# Display.net
KiCad netlist of a schematic drawn in Altium Designer
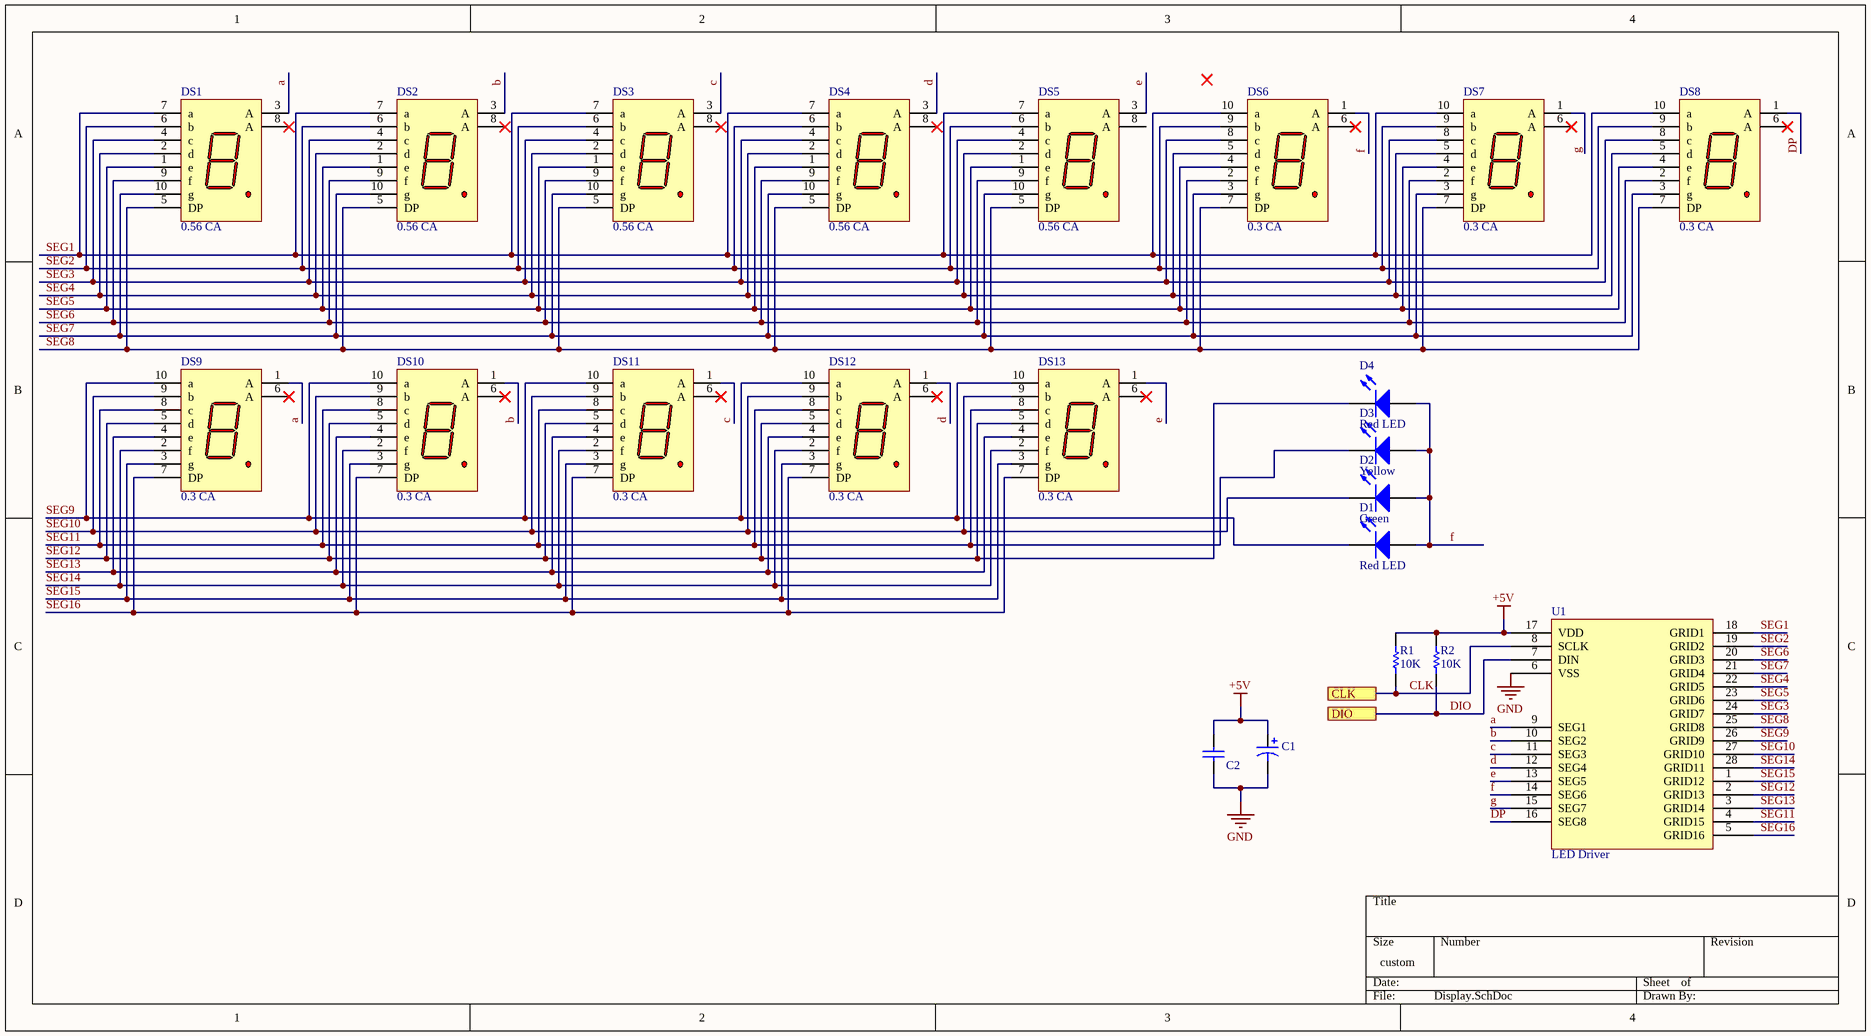
[diagram p0: Display.SchDoc]

(export (version "E")
  (design (tool "Eeschema 10.0.6"))
  (components
    (comp (ref "C1")
      (value "100uF/16V")
      (footprint "C10uF25V")
      (description "100uF/16V Electrolytic Capacitor")
      (fields (field (name "MANUFACTURER PART NUMBER") "Standard"))
      (libsource (lib "Ravi") (part "Capacitor_Electrolytic"))
    )
    (comp (ref "C2")
      (value "0.1uF/50V")
      (footprint "C0603")
      (description "CAP CER 0.1UF 50V X7R 0603")
      (fields (field (name "MANUFACTURER PART NUMBER") "0603B104K500CT"))
      (libsource (lib "Devices") (part "Capacitor_Ceramic"))
    )
    (comp (ref "D1")
      (value "Red LED")
      (footprint "LED-5mm")
      (description "Red 645nm LED Indication - Discrete 2.1V Radial")
      (fields (field (name "MANUFACTURER PART NUMBER") "Standard"))
      (libsource (lib "Ravi") (part "LED"))
    )
    (comp (ref "D2")
      (value "Green")
      (footprint "LED-5mm")
      (description "Green 568nm LED Indication - Discrete 2.2V Radial")
      (fields (field (name "MANUFACTURER PART NUMBER") "Standard"))
      (libsource (lib "Ravi") (part "LED"))
    )
    (comp (ref "D3")
      (value "Yellow")
      (footprint "LED-5mm")
      (description "Yellow 585nm LED Indication - Discrete 1.8V Radial")
      (fields (field (name "MANUFACTURER PART NUMBER") "Standard"))
      (libsource (lib "Ravi") (part "LED"))
    )
    (comp (ref "D4")
      (value "Red LED")
      (footprint "LED-5mm")
      (description "Red 645nm LED Indication - Discrete 2.1V Radial")
      (fields (field (name "MANUFACTURER PART NUMBER") "Standard"))
      (libsource (lib "Ravi") (part "LED"))
    )
    (comp (ref "DS1")
      (value "0.56 CA")
      (footprint "7Segment(0.56)")
      (description "DISPLAY 7SEG 0.56\" RED 10DIP")
      (fields (field (name "MANUFACTURER PART NUMBER") "Standard"))
      (libsource (lib "Ravi") (part "7 Segment_CA_0.56"))
    )
    (comp (ref "DS2")
      (value "0.56 CA")
      (footprint "7Segment(0.56)")
      (description "DISPLAY 7SEG 0.56\" RED 10DIP")
      (fields (field (name "MANUFACTURER PART NUMBER") "Standard"))
      (libsource (lib "Ravi") (part "7 Segment_CA_0.56"))
    )
    (comp (ref "DS3")
      (value "0.56 CA")
      (footprint "7Segment(0.56)")
      (description "DISPLAY 7SEG 0.56\" RED 10DIP")
      (fields (field (name "MANUFACTURER PART NUMBER") "Standard"))
      (libsource (lib "Ravi") (part "7 Segment_CA_0.56"))
    )
    (comp (ref "DS4")
      (value "0.56 CA")
      (footprint "7Segment(0.56)")
      (description "DISPLAY 7SEG 0.56\" RED 10DIP")
      (fields (field (name "MANUFACTURER PART NUMBER") "Standard"))
      (libsource (lib "Ravi") (part "7 Segment_CA_0.56"))
    )
    (comp (ref "DS5")
      (value "0.56 CA")
      (footprint "7Segment(0.56)")
      (description "DISPLAY 7SEG 0.56\" RED 10DIP")
      (fields (field (name "MANUFACTURER PART NUMBER") "Standard"))
      (libsource (lib "Ravi") (part "7 Segment_CA_0.56"))
    )
    (comp (ref "DS6")
      (value "0.3 CA")
      (footprint "7Segment(0.36)")
      (description "DISPLAY 7SEG 0.3\" RED 10DIP")
      (fields (field (name "MANUFACTURER PART NUMBER") "Standard"))
      (libsource (lib "Ravi") (part "7 Segment_CA_0.36"))
    )
    (comp (ref "DS7")
      (value "0.3 CA")
      (footprint "7Segment(0.36)")
      (description "DISPLAY 7SEG 0.3\" RED 10DIP")
      (fields (field (name "MANUFACTURER PART NUMBER") "Standard"))
      (libsource (lib "Ravi") (part "7 Segment_CA_0.36"))
    )
    (comp (ref "DS8")
      (value "0.3 CA")
      (footprint "7Segment(0.36)")
      (description "DISPLAY 7SEG 0.3\" RED 10DIP")
      (fields (field (name "MANUFACTURER PART NUMBER") "Standard"))
      (libsource (lib "Ravi") (part "7 Segment_CA_0.36"))
    )
    (comp (ref "DS9")
      (value "0.3 CA")
      (footprint "7Segment(0.36)")
      (description "DISPLAY 7SEG 0.3\" RED 10DIP")
      (fields (field (name "MANUFACTURER PART NUMBER") "Standard"))
      (libsource (lib "Ravi") (part "7 Segment_CA_0.36"))
    )
    (comp (ref "DS10")
      (value "0.3 CA")
      (footprint "7Segment(0.36)")
      (description "DISPLAY 7SEG 0.3\" RED 10DIP")
      (fields (field (name "MANUFACTURER PART NUMBER") "Standard"))
      (libsource (lib "Ravi") (part "7 Segment_CA_0.36"))
    )
    (comp (ref "DS11")
      (value "0.3 CA")
      (footprint "7Segment(0.36)")
      (description "DISPLAY 7SEG 0.3\" RED 10DIP")
      (fields (field (name "MANUFACTURER PART NUMBER") "Standard"))
      (libsource (lib "Ravi") (part "7 Segment_CA_0.36"))
    )
    (comp (ref "DS12")
      (value "0.3 CA")
      (footprint "7Segment(0.36)")
      (description "DISPLAY 7SEG 0.3\" RED 10DIP")
      (fields (field (name "MANUFACTURER PART NUMBER") "Standard"))
      (libsource (lib "Ravi") (part "7 Segment_CA_0.36"))
    )
    (comp (ref "DS13")
      (value "0.3 CA")
      (footprint "7Segment(0.36)")
      (description "DISPLAY 7SEG 0.3\" RED 10DIP")
      (fields (field (name "MANUFACTURER PART NUMBER") "Standard"))
      (libsource (lib "Ravi") (part "7 Segment_CA_0.36"))
    )
    (comp (ref "R1")
      (value "10K")
      (footprint "R0603")
      (description "RES 10K OHM 1% 1/10W 0603")
      (fields (field (name "MANUFACTURER PART NUMBER") "CR16-1002-FL"))
      (libsource (lib "Devices") (part "Res1"))
    )
    (comp (ref "R2")
      (value "10K")
      (footprint "R0603")
      (description "RES 10K OHM 1% 1/10W 0603")
      (fields (field (name "MANUFACTURER PART NUMBER") "CR16-1002-FL"))
      (libsource (lib "Devices") (part "Res1"))
    )
    (comp (ref "U1")
      (value "LED Driver")
      (footprint "SOP28")
      (description "LED Drive Control Circuit")
      (fields (field (name "MANUFACTURER PART NUMBER") "TM1640"))
      (libsource (lib "Ravi") (part "TMXXXX"))
    )
  )
  (nets
    (net (code "1") (name "+5V") (class "Default")
      (node (ref "C1") (pin "1") (pinfunction "1_1") (pintype "passive"))
      (node (ref "C2") (pin "2") (pinfunction "2_2") (pintype "passive"))
      (node (ref "R1") (pin "2") (pinfunction "2_2") (pintype "passive"))
      (node (ref "R2") (pin "2") (pinfunction "2_2") (pintype "passive"))
      (node (ref "U1") (pin "17") (pinfunction "VDD_17") (pintype "power_in"))
    )
    (net (code "2") (name "/CLK") (class "Default")
      (node (ref "R1") (pin "1") (pinfunction "1_1") (pintype "passive"))
      (node (ref "U1") (pin "8") (pinfunction "SCLK_8") (pintype "passive"))
    )
    (net (code "3") (name "/DIO") (class "Default")
      (node (ref "R2") (pin "1") (pinfunction "1_1") (pintype "passive"))
      (node (ref "U1") (pin "7") (pinfunction "DIN_7") (pintype "passive"))
    )
    (net (code "4") (name "/DP") (class "Default")
      (node (ref "DS8") (pin "1") (pinfunction "A_1") (pintype "passive"))
      (node (ref "U1") (pin "16") (pinfunction "SEG8_16") (pintype "open_collector"))
    )
    (net (code "5") (name "/SEG1") (class "Default")
      (node (ref "DS1") (pin "7") (pinfunction "a_7") (pintype "passive"))
      (node (ref "DS2") (pin "7") (pinfunction "a_7") (pintype "passive"))
      (node (ref "DS3") (pin "7") (pinfunction "a_7") (pintype "passive"))
      (node (ref "DS4") (pin "7") (pinfunction "a_7") (pintype "passive"))
      (node (ref "DS5") (pin "7") (pinfunction "a_7") (pintype "passive"))
      (node (ref "DS6") (pin "10") (pinfunction "a_10") (pintype "passive"))
      (node (ref "DS7") (pin "10") (pinfunction "a_10") (pintype "passive"))
      (node (ref "DS8") (pin "10") (pinfunction "a_10") (pintype "passive"))
      (node (ref "U1") (pin "18") (pinfunction "GRID1_18") (pintype "open_collector"))
    )
    (net (code "6") (name "/SEG2") (class "Default")
      (node (ref "DS1") (pin "6") (pinfunction "b_6") (pintype "passive"))
      (node (ref "DS2") (pin "6") (pinfunction "b_6") (pintype "passive"))
      (node (ref "DS3") (pin "6") (pinfunction "b_6") (pintype "passive"))
      (node (ref "DS4") (pin "6") (pinfunction "b_6") (pintype "passive"))
      (node (ref "DS5") (pin "6") (pinfunction "b_6") (pintype "passive"))
      (node (ref "DS6") (pin "9") (pinfunction "b_9") (pintype "passive"))
      (node (ref "DS7") (pin "9") (pinfunction "b_9") (pintype "passive"))
      (node (ref "DS8") (pin "9") (pinfunction "b_9") (pintype "passive"))
      (node (ref "U1") (pin "19") (pinfunction "GRID2_19") (pintype "open_collector"))
    )
    (net (code "7") (name "/SEG3") (class "Default")
      (node (ref "DS1") (pin "4") (pinfunction "c_4") (pintype "passive"))
      (node (ref "DS2") (pin "4") (pinfunction "c_4") (pintype "passive"))
      (node (ref "DS3") (pin "4") (pinfunction "c_4") (pintype "passive"))
      (node (ref "DS4") (pin "4") (pinfunction "c_4") (pintype "passive"))
      (node (ref "DS5") (pin "4") (pinfunction "c_4") (pintype "passive"))
      (node (ref "DS6") (pin "8") (pinfunction "c_8") (pintype "passive"))
      (node (ref "DS7") (pin "8") (pinfunction "c_8") (pintype "passive"))
      (node (ref "DS8") (pin "8") (pinfunction "c_8") (pintype "passive"))
      (node (ref "U1") (pin "24") (pinfunction "GRID7_24") (pintype "open_collector"))
    )
    (net (code "8") (name "/SEG4") (class "Default")
      (node (ref "DS1") (pin "2") (pinfunction "d_2") (pintype "passive"))
      (node (ref "DS2") (pin "2") (pinfunction "d_2") (pintype "passive"))
      (node (ref "DS3") (pin "2") (pinfunction "d_2") (pintype "passive"))
      (node (ref "DS4") (pin "2") (pinfunction "d_2") (pintype "passive"))
      (node (ref "DS5") (pin "2") (pinfunction "d_2") (pintype "passive"))
      (node (ref "DS6") (pin "5") (pinfunction "d_5") (pintype "passive"))
      (node (ref "DS7") (pin "5") (pinfunction "d_5") (pintype "passive"))
      (node (ref "DS8") (pin "5") (pinfunction "d_5") (pintype "passive"))
      (node (ref "U1") (pin "22") (pinfunction "GRID5_22") (pintype "open_collector"))
    )
    (net (code "9") (name "/SEG5") (class "Default")
      (node (ref "DS1") (pin "1") (pinfunction "e_1") (pintype "passive"))
      (node (ref "DS2") (pin "1") (pinfunction "e_1") (pintype "passive"))
      (node (ref "DS3") (pin "1") (pinfunction "e_1") (pintype "passive"))
      (node (ref "DS4") (pin "1") (pinfunction "e_1") (pintype "passive"))
      (node (ref "DS5") (pin "1") (pinfunction "e_1") (pintype "passive"))
      (node (ref "DS6") (pin "4") (pinfunction "e_4") (pintype "passive"))
      (node (ref "DS7") (pin "4") (pinfunction "e_4") (pintype "passive"))
      (node (ref "DS8") (pin "4") (pinfunction "e_4") (pintype "passive"))
      (node (ref "U1") (pin "23") (pinfunction "GRID6_23") (pintype "open_collector"))
    )
    (net (code "10") (name "/SEG6") (class "Default")
      (node (ref "DS1") (pin "9") (pinfunction "f_9") (pintype "passive"))
      (node (ref "DS2") (pin "9") (pinfunction "f_9") (pintype "passive"))
      (node (ref "DS3") (pin "9") (pinfunction "f_9") (pintype "passive"))
      (node (ref "DS4") (pin "9") (pinfunction "f_9") (pintype "passive"))
      (node (ref "DS5") (pin "9") (pinfunction "f_9") (pintype "passive"))
      (node (ref "DS6") (pin "2") (pinfunction "f_2") (pintype "passive"))
      (node (ref "DS7") (pin "2") (pinfunction "f_2") (pintype "passive"))
      (node (ref "DS8") (pin "2") (pinfunction "f_2") (pintype "passive"))
      (node (ref "U1") (pin "20") (pinfunction "GRID3_20") (pintype "open_collector"))
    )
    (net (code "11") (name "/SEG7") (class "Default")
      (node (ref "DS1") (pin "10") (pinfunction "g_10") (pintype "passive"))
      (node (ref "DS2") (pin "10") (pinfunction "g_10") (pintype "passive"))
      (node (ref "DS3") (pin "10") (pinfunction "g_10") (pintype "passive"))
      (node (ref "DS4") (pin "10") (pinfunction "g_10") (pintype "passive"))
      (node (ref "DS5") (pin "10") (pinfunction "g_10") (pintype "passive"))
      (node (ref "DS6") (pin "3") (pinfunction "g_3") (pintype "passive"))
      (node (ref "DS7") (pin "3") (pinfunction "g_3") (pintype "passive"))
      (node (ref "DS8") (pin "3") (pinfunction "g_3") (pintype "passive"))
      (node (ref "U1") (pin "21") (pinfunction "GRID4_21") (pintype "open_collector"))
    )
    (net (code "12") (name "/SEG8") (class "Default")
      (node (ref "DS1") (pin "5") (pinfunction "DP_5") (pintype "passive"))
      (node (ref "DS2") (pin "5") (pinfunction "DP_5") (pintype "passive"))
      (node (ref "DS3") (pin "5") (pinfunction "DP_5") (pintype "passive"))
      (node (ref "DS4") (pin "5") (pinfunction "DP_5") (pintype "passive"))
      (node (ref "DS5") (pin "5") (pinfunction "DP_5") (pintype "passive"))
      (node (ref "DS6") (pin "7") (pinfunction "DP_7") (pintype "passive"))
      (node (ref "DS7") (pin "7") (pinfunction "DP_7") (pintype "passive"))
      (node (ref "DS8") (pin "7") (pinfunction "DP_7") (pintype "passive"))
      (node (ref "U1") (pin "25") (pinfunction "GRID8_25") (pintype "open_collector"))
    )
    (net (code "13") (name "/SEG9") (class "Default")
      (node (ref "D1") (pin "2") (pinfunction "K_2") (pintype "passive"))
      (node (ref "DS10") (pin "10") (pinfunction "a_10") (pintype "passive"))
      (node (ref "DS11") (pin "10") (pinfunction "a_10") (pintype "passive"))
      (node (ref "DS12") (pin "10") (pinfunction "a_10") (pintype "passive"))
      (node (ref "DS13") (pin "10") (pinfunction "a_10") (pintype "passive"))
      (node (ref "DS9") (pin "10") (pinfunction "a_10") (pintype "passive"))
      (node (ref "U1") (pin "26") (pinfunction "GRID9_26") (pintype "open_collector"))
    )
    (net (code "14") (name "/SEG10") (class "Default")
      (node (ref "D2") (pin "2") (pinfunction "K_2") (pintype "passive"))
      (node (ref "DS10") (pin "9") (pinfunction "b_9") (pintype "passive"))
      (node (ref "DS11") (pin "9") (pinfunction "b_9") (pintype "passive"))
      (node (ref "DS12") (pin "9") (pinfunction "b_9") (pintype "passive"))
      (node (ref "DS13") (pin "9") (pinfunction "b_9") (pintype "passive"))
      (node (ref "DS9") (pin "9") (pinfunction "b_9") (pintype "passive"))
      (node (ref "U1") (pin "27") (pinfunction "GRID10_27") (pintype "open_collector"))
    )
    (net (code "15") (name "/SEG11") (class "Default")
      (node (ref "D3") (pin "2") (pinfunction "K_2") (pintype "passive"))
      (node (ref "DS10") (pin "8") (pinfunction "c_8") (pintype "passive"))
      (node (ref "DS11") (pin "8") (pinfunction "c_8") (pintype "passive"))
      (node (ref "DS12") (pin "8") (pinfunction "c_8") (pintype "passive"))
      (node (ref "DS13") (pin "8") (pinfunction "c_8") (pintype "passive"))
      (node (ref "DS9") (pin "8") (pinfunction "c_8") (pintype "passive"))
      (node (ref "U1") (pin "4") (pinfunction "GRID15_4") (pintype "open_collector"))
    )
    (net (code "16") (name "/SEG12") (class "Default")
      (node (ref "D4") (pin "2") (pinfunction "K_2") (pintype "passive"))
      (node (ref "DS10") (pin "5") (pinfunction "d_5") (pintype "passive"))
      (node (ref "DS11") (pin "5") (pinfunction "d_5") (pintype "passive"))
      (node (ref "DS12") (pin "5") (pinfunction "d_5") (pintype "passive"))
      (node (ref "DS13") (pin "5") (pinfunction "d_5") (pintype "passive"))
      (node (ref "DS9") (pin "5") (pinfunction "d_5") (pintype "passive"))
      (node (ref "U1") (pin "2") (pinfunction "GRID13_2") (pintype "open_collector"))
    )
    (net (code "17") (name "/SEG13") (class "Default")
      (node (ref "DS10") (pin "4") (pinfunction "e_4") (pintype "passive"))
      (node (ref "DS11") (pin "4") (pinfunction "e_4") (pintype "passive"))
      (node (ref "DS12") (pin "4") (pinfunction "e_4") (pintype "passive"))
      (node (ref "DS13") (pin "4") (pinfunction "e_4") (pintype "passive"))
      (node (ref "DS9") (pin "4") (pinfunction "e_4") (pintype "passive"))
      (node (ref "U1") (pin "3") (pinfunction "GRID14_3") (pintype "open_collector"))
    )
    (net (code "18") (name "/SEG14") (class "Default")
      (node (ref "DS10") (pin "2") (pinfunction "f_2") (pintype "passive"))
      (node (ref "DS11") (pin "2") (pinfunction "f_2") (pintype "passive"))
      (node (ref "DS12") (pin "2") (pinfunction "f_2") (pintype "passive"))
      (node (ref "DS13") (pin "2") (pinfunction "f_2") (pintype "passive"))
      (node (ref "DS9") (pin "2") (pinfunction "f_2") (pintype "passive"))
      (node (ref "U1") (pin "28") (pinfunction "GRID11_28") (pintype "open_collector"))
    )
    (net (code "19") (name "/SEG15") (class "Default")
      (node (ref "DS10") (pin "3") (pinfunction "g_3") (pintype "passive"))
      (node (ref "DS11") (pin "3") (pinfunction "g_3") (pintype "passive"))
      (node (ref "DS12") (pin "3") (pinfunction "g_3") (pintype "passive"))
      (node (ref "DS13") (pin "3") (pinfunction "g_3") (pintype "passive"))
      (node (ref "DS9") (pin "3") (pinfunction "g_3") (pintype "passive"))
      (node (ref "U1") (pin "1") (pinfunction "GRID12_1") (pintype "open_collector"))
    )
    (net (code "20") (name "/SEG16") (class "Default")
      (node (ref "DS10") (pin "7") (pinfunction "DP_7") (pintype "passive"))
      (node (ref "DS11") (pin "7") (pinfunction "DP_7") (pintype "passive"))
      (node (ref "DS12") (pin "7") (pinfunction "DP_7") (pintype "passive"))
      (node (ref "DS13") (pin "7") (pinfunction "DP_7") (pintype "passive"))
      (node (ref "DS9") (pin "7") (pinfunction "DP_7") (pintype "passive"))
      (node (ref "U1") (pin "5") (pinfunction "GRID16_5") (pintype "open_collector"))
    )
    (net (code "21") (name "/a") (class "Default")
      (node (ref "DS1") (pin "3") (pinfunction "A_3") (pintype "passive"))
      (node (ref "DS9") (pin "1") (pinfunction "A_1") (pintype "passive"))
      (node (ref "U1") (pin "9") (pinfunction "SEG1_9") (pintype "open_collector"))
    )
    (net (code "22") (name "/b") (class "Default")
      (node (ref "DS10") (pin "1") (pinfunction "A_1") (pintype "passive"))
      (node (ref "DS2") (pin "3") (pinfunction "A_3") (pintype "passive"))
      (node (ref "U1") (pin "10") (pinfunction "SEG2_10") (pintype "open_collector"))
    )
    (net (code "23") (name "/c") (class "Default")
      (node (ref "DS11") (pin "1") (pinfunction "A_1") (pintype "passive"))
      (node (ref "DS3") (pin "3") (pinfunction "A_3") (pintype "passive"))
      (node (ref "U1") (pin "11") (pinfunction "SEG3_11") (pintype "open_collector"))
    )
    (net (code "24") (name "/d") (class "Default")
      (node (ref "DS12") (pin "1") (pinfunction "A_1") (pintype "passive"))
      (node (ref "DS4") (pin "3") (pinfunction "A_3") (pintype "passive"))
      (node (ref "U1") (pin "12") (pinfunction "SEG4_12") (pintype "open_collector"))
    )
    (net (code "25") (name "/e") (class "Default")
      (node (ref "DS13") (pin "1") (pinfunction "A_1") (pintype "passive"))
      (node (ref "DS5") (pin "3") (pinfunction "A_3") (pintype "passive"))
      (node (ref "U1") (pin "13") (pinfunction "SEG5_13") (pintype "open_collector"))
    )
    (net (code "26") (name "/f") (class "Default")
      (node (ref "D1") (pin "1") (pinfunction "A_1") (pintype "passive"))
      (node (ref "D2") (pin "1") (pinfunction "A_1") (pintype "passive"))
      (node (ref "D3") (pin "1") (pinfunction "A_1") (pintype "passive"))
      (node (ref "D4") (pin "1") (pinfunction "A_1") (pintype "passive"))
      (node (ref "DS6") (pin "1") (pinfunction "A_1") (pintype "passive"))
      (node (ref "U1") (pin "14") (pinfunction "SEG6_14") (pintype "open_collector"))
    )
    (net (code "27") (name "/g") (class "Default")
      (node (ref "DS7") (pin "1") (pinfunction "A_1") (pintype "passive"))
      (node (ref "U1") (pin "15") (pinfunction "SEG7_15") (pintype "open_collector"))
    )
    (net (code "28") (name "GND") (class "Default")
      (node (ref "C1") (pin "2") (pinfunction "2_2") (pintype "passive"))
      (node (ref "C2") (pin "1") (pinfunction "1_1") (pintype "passive"))
      (node (ref "U1") (pin "6") (pinfunction "VSS_6") (pintype "power_in"))
    )
    (net (code "29") (name "unconnected-(DS1-A-Pad8)") (class "Default")
      (node (ref "DS1") (pin "8") (pinfunction "A_8") (pintype "passive+no_connect"))
    )
    (net (code "30") (name "unconnected-(DS2-A-Pad8)") (class "Default")
      (node (ref "DS2") (pin "8") (pinfunction "A_8") (pintype "passive+no_connect"))
    )
    (net (code "31") (name "unconnected-(DS3-A-Pad8)") (class "Default")
      (node (ref "DS3") (pin "8") (pinfunction "A_8") (pintype "passive+no_connect"))
    )
    (net (code "32") (name "unconnected-(DS4-A-Pad8)") (class "Default")
      (node (ref "DS4") (pin "8") (pinfunction "A_8") (pintype "passive+no_connect"))
    )
    (net (code "33") (name "unconnected-(DS5-A-Pad8)") (class "Default")
      (node (ref "DS5") (pin "8") (pinfunction "A_8") (pintype "passive"))
    )
    (net (code "34") (name "unconnected-(DS6-A-Pad6)") (class "Default")
      (node (ref "DS6") (pin "6") (pinfunction "A_6") (pintype "passive+no_connect"))
    )
    (net (code "35") (name "unconnected-(DS7-A-Pad6)") (class "Default")
      (node (ref "DS7") (pin "6") (pinfunction "A_6") (pintype "passive+no_connect"))
    )
    (net (code "36") (name "unconnected-(DS8-A-Pad6)") (class "Default")
      (node (ref "DS8") (pin "6") (pinfunction "A_6") (pintype "passive+no_connect"))
    )
    (net (code "37") (name "unconnected-(DS9-A-Pad6)") (class "Default")
      (node (ref "DS9") (pin "6") (pinfunction "A_6") (pintype "passive+no_connect"))
    )
    (net (code "38") (name "unconnected-(DS10-A-Pad6)") (class "Default")
      (node (ref "DS10") (pin "6") (pinfunction "A_6") (pintype "passive+no_connect"))
    )
    (net (code "39") (name "unconnected-(DS11-A-Pad6)") (class "Default")
      (node (ref "DS11") (pin "6") (pinfunction "A_6") (pintype "passive+no_connect"))
    )
    (net (code "40") (name "unconnected-(DS12-A-Pad6)") (class "Default")
      (node (ref "DS12") (pin "6") (pinfunction "A_6") (pintype "passive+no_connect"))
    )
    (net (code "41") (name "unconnected-(DS13-A-Pad6)") (class "Default")
      (node (ref "DS13") (pin "6") (pinfunction "A_6") (pintype "passive+no_connect"))
    )
  )
)
